# 05_SENSORS.net
KiCad netlist of a schematic drawn in Altium Designer
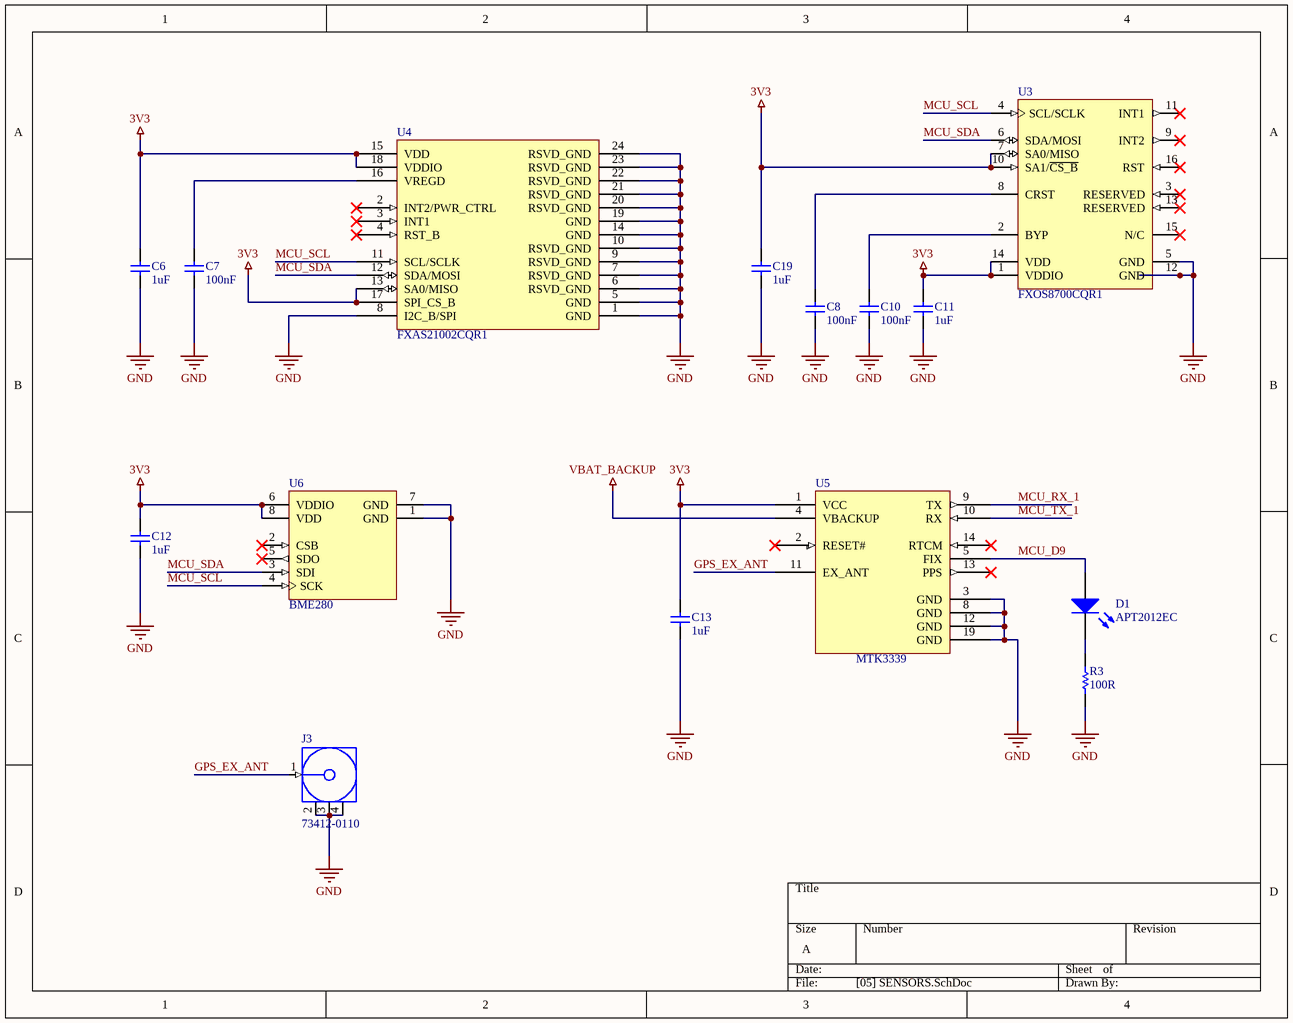
[diagram p0: [05] SENSORS.SchDoc]

(export (version "E")
  (design (tool "Eeschema 10.0.6"))
  (components
    (comp (ref "C6")
      (value "1uF")
      (footprint "INCH 0805 - METRIC 2012 - H140")
      (description "CAP SMD 1uF 25V 10% 0805")
      (fields
        (field (name "MANUFACTURER") "Murata")
        (field (name "MANUFACTURER PART NUMBER") "GCM21BR71E105KA56L")
      )
      (libsource (lib "Capacitors") (part "GCM21BR71E105KA56L"))
    )
    (comp (ref "C7")
      (value "100nF")
      (footprint "INCH 0805 - METRIC 2012 - H120")
      (description "CAP CER 0.1UF 100V X7R 0805")
      (fields
        (field (name "MANUFACTURER") "KEMET")
        (field (name "MANUFACTURER PART NUMBER") "C0805C104K1RACTU")
      )
      (libsource (lib "Capacitors") (part "C0805C104K1RACTU"))
    )
    (comp (ref "C8")
      (value "100nF")
      (footprint "INCH 0805 - METRIC 2012 - H120")
      (description "CAP CER 0.1UF 100V X7R 0805")
      (fields
        (field (name "MANUFACTURER") "KEMET")
        (field (name "MANUFACTURER PART NUMBER") "C0805C104K1RACTU")
      )
      (libsource (lib "Capacitors") (part "C0805C104K1RACTU"))
    )
    (comp (ref "C10")
      (value "100nF")
      (footprint "INCH 0805 - METRIC 2012 - H120")
      (description "CAP CER 0.1UF 100V X7R 0805")
      (fields
        (field (name "MANUFACTURER") "KEMET")
        (field (name "MANUFACTURER PART NUMBER") "C0805C104K1RACTU")
      )
      (libsource (lib "Capacitors") (part "C0805C104K1RACTU"))
    )
    (comp (ref "C11")
      (value "1uF")
      (footprint "INCH 0805 - METRIC 2012 - H140")
      (description "CAP SMD 1uF 25V 10% 0805")
      (fields
        (field (name "MANUFACTURER") "Murata")
        (field (name "MANUFACTURER PART NUMBER") "GCM21BR71E105KA56L")
      )
      (libsource (lib "Capacitors") (part "GCM21BR71E105KA56L"))
    )
    (comp (ref "C12")
      (value "1uF")
      (footprint "INCH 0805 - METRIC 2012 - H140")
      (description "CAP SMD 1uF 25V 10% 0805")
      (fields
        (field (name "MANUFACTURER") "Murata")
        (field (name "MANUFACTURER PART NUMBER") "GCM21BR71E105KA56L")
      )
      (libsource (lib "Capacitors") (part "GCM21BR71E105KA56L"))
    )
    (comp (ref "C13")
      (value "1uF")
      (footprint "INCH 0805 - METRIC 2012 - H140")
      (description "CAP SMD 1uF 25V 10% 0805")
      (fields
        (field (name "MANUFACTURER") "Murata")
        (field (name "MANUFACTURER PART NUMBER") "GCM21BR71E105KA56L")
      )
      (libsource (lib "Capacitors") (part "GCM21BR71E105KA56L"))
    )
    (comp (ref "C19")
      (value "1uF")
      (footprint "INCH 0805 - METRIC 2012 - H140")
      (description "CAP SMD 1uF 25V 10% 0805")
      (fields
        (field (name "MANUFACTURER") "Murata")
        (field (name "MANUFACTURER PART NUMBER") "GCM21BR71E105KA56L")
      )
      (libsource (lib "Capacitors") (part "GCM21BR71E105KA56L"))
    )
    (comp (ref "D1")
      (value "APT2012EC")
      (footprint "LED - 0805 - GREEN")
      (description "LED RED CLEAR CHIP SMD")
      (fields (field (name "MANUFACTURER") "Kingbright"))
      (libsource (lib "LEDs") (part "APT2012EC"))
    )
    (comp (ref "J3")
      (value "73412-0110")
      (footprint "MOLX-73412-0110_V")
      (description "MCRF, PCB Vertical Jack Receptacle, 50 Ohm, 4-Pin SMD, RoHS, Tape and Reel")
      (libsource (lib "Altium Content Vault") (part "MOLX-73412-0110"))
    )
    (comp (ref "R3")
      (value "100R")
      (footprint "INCH 0805 - METRIC 2012 - H070")
      (description "RES SMD 100 OHM 5% 1/2W 0805")
      (fields
        (field (name "MANUFACTURER") "Panasonic")
        (field (name "MANUFACTURER PART NUMBER") "ERJ-P06J101V")
      )
      (libsource (lib "Resistors") (part "ERJ-P06J101V"))
    )
    (comp (ref "U3")
      (value "FXOS8700CQR1")
      (footprint "FREE-QFN-16-3000X3000DE_V")
      (fields (field (name "MANUFACTURER") "Freescale"))
      (libsource (lib "Altium Content Vault") (part "FREE-FXOS8700CQR1-16"))
    )
    (comp (ref "U4")
      (value "FXAS21002CQR1")
      (footprint "FXAS21002CQR1")
      (description "NXP Precision 3 Axis Gyro I2C")
      (libsource (lib "ICs - Sensors") (part "FXAS21002CQR1"))
    )
    (comp (ref "U5")
      (value "MTK3339")
      (footprint "MTK3339")
      (description "Ultimate GPS Module 66 channel 10 Hz")
      (libsource (lib "ICs - Sensors") (part "MTK3339"))
    )
    (comp (ref "U6")
      (value "BME280")
      (footprint "BOSC-BME280-8_V")
      (fields (field (name "MANUFACTURER") "Bosch Sensortec"))
      (libsource (lib "Altium Content Vault") (part "BOSC-BME280-8"))
    )
  )
  (nets
    (net (code "1") (name "/GPS_EX_ANT") (class "Default")
      (node (ref "J3") (pin "1") (pinfunction "SIGNAL_1") (pintype "input"))
      (node (ref "U5") (pin "11") (pinfunction "EX_ANT_11") (pintype "passive"))
    )
    (net (code "2") (name "/MCU_D9") (class "Default")
      (node (ref "D1") (pin "A") (pintype "passive"))
      (node (ref "U5") (pin "5") (pinfunction "FIX_5") (pintype "power_in"))
    )
    (net (code "3") (name "/MCU_RX_1") (class "Default")
      (node (ref "U5") (pin "9") (pinfunction "TX_9") (pintype "output"))
    )
    (net (code "4") (name "/MCU_SCL") (class "Default")
      (node (ref "U3") (pin "4") (pinfunction "SCL/SCLK_4") (pintype "input"))
      (node (ref "U4") (pin "11") (pinfunction "SCL/SCLK_11") (pintype "input"))
      (node (ref "U6") (pin "4") (pinfunction "SCK_4") (pintype "input"))
    )
    (net (code "5") (name "/MCU_SDA") (class "Default")
      (node (ref "U3") (pin "6") (pinfunction "SDA/MOSI_6") (pintype "bidirectional"))
      (node (ref "U4") (pin "12") (pinfunction "SDA/MOSI_12") (pintype "bidirectional"))
      (node (ref "U6") (pin "3") (pinfunction "SDI_3") (pintype "input"))
    )
    (net (code "6") (name "/MCU_TX_1") (class "Default")
      (node (ref "U5") (pin "10") (pinfunction "RX_10") (pintype "input"))
    )
    (net (code "7") (name "3V3") (class "Default")
      (node (ref "C11") (pin "2") (pintype "passive"))
      (node (ref "C12") (pin "2") (pintype "passive"))
      (node (ref "C13") (pin "2") (pintype "passive"))
      (node (ref "C19") (pin "2") (pintype "passive"))
      (node (ref "C6") (pin "2") (pintype "passive"))
      (node (ref "U3") (pin "1") (pinfunction "VDDIO_1") (pintype "power_in"))
      (node (ref "U3") (pin "10") (pinfunction "SA1/~{CS_B}_10") (pintype "input"))
      (node (ref "U3") (pin "14") (pinfunction "VDD_14") (pintype "power_in"))
      (node (ref "U3") (pin "7") (pinfunction "SA0/MISO_7") (pintype "bidirectional"))
      (node (ref "U4") (pin "13") (pinfunction "SA0/MISO_13") (pintype "bidirectional"))
      (node (ref "U4") (pin "15") (pinfunction "VDD_15") (pintype "power_in"))
      (node (ref "U4") (pin "17") (pinfunction "SPI_CS_B_17") (pintype "power_in"))
      (node (ref "U4") (pin "18") (pinfunction "VDDIO_18") (pintype "power_in"))
      (node (ref "U5") (pin "1") (pinfunction "VCC_1") (pintype "power_in"))
      (node (ref "U6") (pin "6") (pinfunction "VDDIO_6") (pintype "power_in"))
      (node (ref "U6") (pin "8") (pinfunction "VDD_8") (pintype "power_in"))
    )
    (net (code "8") (name "GND") (class "Default")
      (node (ref "C10") (pin "1") (pintype "passive"))
      (node (ref "C11") (pin "1") (pintype "passive"))
      (node (ref "C12") (pin "1") (pintype "passive"))
      (node (ref "C13") (pin "1") (pintype "passive"))
      (node (ref "C19") (pin "1") (pintype "passive"))
      (node (ref "C6") (pin "1") (pintype "passive"))
      (node (ref "C7") (pin "1") (pintype "passive"))
      (node (ref "C8") (pin "1") (pintype "passive"))
      (node (ref "J3") (pin "2") (pinfunction "GND_2") (pintype "power_in"))
      (node (ref "J3") (pin "3") (pinfunction "GND_3") (pintype "power_in"))
      (node (ref "J3") (pin "4") (pinfunction "GND_4") (pintype "power_in"))
      (node (ref "R3") (pin "1") (pintype "passive"))
      (node (ref "U3") (pin "12") (pinfunction "GND_12") (pintype "power_in"))
      (node (ref "U3") (pin "5") (pinfunction "GND_5") (pintype "power_in"))
      (node (ref "U4") (pin "1") (pinfunction "GND_1") (pintype "power_in"))
      (node (ref "U4") (pin "10") (pinfunction "RSVD_GND_10") (pintype "power_in"))
      (node (ref "U4") (pin "14") (pinfunction "GND_14") (pintype "power_in"))
      (node (ref "U4") (pin "19") (pinfunction "GND_19") (pintype "power_in"))
      (node (ref "U4") (pin "20") (pinfunction "RSVD_GND_20") (pintype "power_in"))
      (node (ref "U4") (pin "21") (pinfunction "RSVD_GND_21") (pintype "power_in"))
      (node (ref "U4") (pin "22") (pinfunction "RSVD_GND_22") (pintype "power_in"))
      (node (ref "U4") (pin "23") (pinfunction "RSVD_GND_23") (pintype "power_in"))
      (node (ref "U4") (pin "24") (pinfunction "RSVD_GND_24") (pintype "power_in"))
      (node (ref "U4") (pin "5") (pinfunction "GND_5") (pintype "power_in"))
      (node (ref "U4") (pin "6") (pinfunction "RSVD_GND_6") (pintype "power_in"))
      (node (ref "U4") (pin "7") (pinfunction "RSVD_GND_7") (pintype "power_in"))
      (node (ref "U4") (pin "8") (pinfunction "I2C_B/SPI_8") (pintype "power_in"))
      (node (ref "U4") (pin "9") (pinfunction "RSVD_GND_9") (pintype "power_in"))
      (node (ref "U5") (pin "12") (pinfunction "GND_12") (pintype "power_in"))
      (node (ref "U5") (pin "19") (pinfunction "GND_19") (pintype "power_in"))
      (node (ref "U5") (pin "3") (pinfunction "GND_3") (pintype "power_in"))
      (node (ref "U5") (pin "8") (pinfunction "GND_8") (pintype "power_in"))
      (node (ref "U6") (pin "1") (pinfunction "GND_1") (pintype "power_in"))
      (node (ref "U6") (pin "7") (pinfunction "GND_7") (pintype "power_in"))
    )
    (net (code "9") (name "Net-(D1-PadC)") (class "Default")
      (node (ref "D1") (pin "C") (pintype "passive"))
      (node (ref "R3") (pin "2") (pintype "passive"))
    )
    (net (code "10") (name "Net-(U3-BYP)") (class "Default")
      (node (ref "C10") (pin "2") (pintype "passive"))
      (node (ref "U3") (pin "2") (pinfunction "BYP_2") (pintype "passive"))
    )
    (net (code "11") (name "Net-(U3-CRST)") (class "Default")
      (node (ref "C8") (pin "2") (pintype "passive"))
      (node (ref "U3") (pin "8") (pinfunction "CRST_8") (pintype "passive"))
    )
    (net (code "12") (name "Net-(U4-VREGD)") (class "Default")
      (node (ref "C7") (pin "2") (pintype "passive"))
      (node (ref "U4") (pin "16") (pinfunction "VREGD_16") (pintype "power_in"))
    )
    (net (code "13") (name "VBAT_BACKUP") (class "Default")
      (node (ref "U5") (pin "4") (pinfunction "VBACKUP_4") (pintype "power_in"))
    )
    (net (code "14") (name "unconnected-(U3-INT1-Pad11)") (class "Default")
      (node (ref "U3") (pin "11") (pinfunction "INT1_11") (pintype "output+no_connect"))
    )
    (net (code "15") (name "unconnected-(U3-INT2-Pad9)") (class "Default")
      (node (ref "U3") (pin "9") (pinfunction "INT2_9") (pintype "output+no_connect"))
    )
    (net (code "16") (name "unconnected-(U3-N{slash}C-Pad15)") (class "Default")
      (node (ref "U3") (pin "15") (pinfunction "N/C_15") (pintype "passive+no_connect"))
    )
    (net (code "17") (name "unconnected-(U3-RESERVED-Pad3)") (class "Default")
      (node (ref "U3") (pin "3") (pinfunction "RESERVED_3") (pintype "input+no_connect"))
    )
    (net (code "18") (name "unconnected-(U3-RESERVED-Pad13)") (class "Default")
      (node (ref "U3") (pin "13") (pinfunction "RESERVED_13") (pintype "input+no_connect"))
    )
    (net (code "19") (name "unconnected-(U3-RST-Pad16)") (class "Default")
      (node (ref "U3") (pin "16") (pinfunction "RST_16") (pintype "input+no_connect"))
    )
    (net (code "20") (name "unconnected-(U4-INT1-Pad3)") (class "Default")
      (node (ref "U4") (pin "3") (pinfunction "INT1_3") (pintype "input+no_connect"))
    )
    (net (code "21") (name "unconnected-(U4-INT2{slash}PWR_CTRL-Pad2)") (class "Default")
      (node (ref "U4") (pin "2") (pinfunction "INT2/PWR_CTRL_2") (pintype "input+no_connect"))
    )
    (net (code "22") (name "unconnected-(U4-RST_B-Pad4)") (class "Default")
      (node (ref "U4") (pin "4") (pinfunction "RST_B_4") (pintype "input+no_connect"))
    )
    (net (code "23") (name "unconnected-(U5-PPS-Pad13)") (class "Default")
      (node (ref "U5") (pin "13") (pinfunction "PPS_13") (pintype "output+no_connect"))
    )
    (net (code "24") (name "unconnected-(U5-RESET#-Pad2)") (class "Default")
      (node (ref "U5") (pin "2") (pinfunction "RESET#_2") (pintype "input+no_connect"))
    )
    (net (code "25") (name "unconnected-(U5-RTCM-Pad14)") (class "Default")
      (node (ref "U5") (pin "14") (pinfunction "RTCM_14") (pintype "input+no_connect"))
    )
    (net (code "26") (name "unconnected-(U6-CSB-Pad2)") (class "Default")
      (node (ref "U6") (pin "2") (pinfunction "CSB_2") (pintype "input+no_connect"))
    )
    (net (code "27") (name "unconnected-(U6-SDO-Pad5)") (class "Default")
      (node (ref "U6") (pin "5") (pinfunction "SDO_5") (pintype "output+no_connect"))
    )
  )
)
